# 3.net
KiCad netlist of a schematic drawn in EAGLE
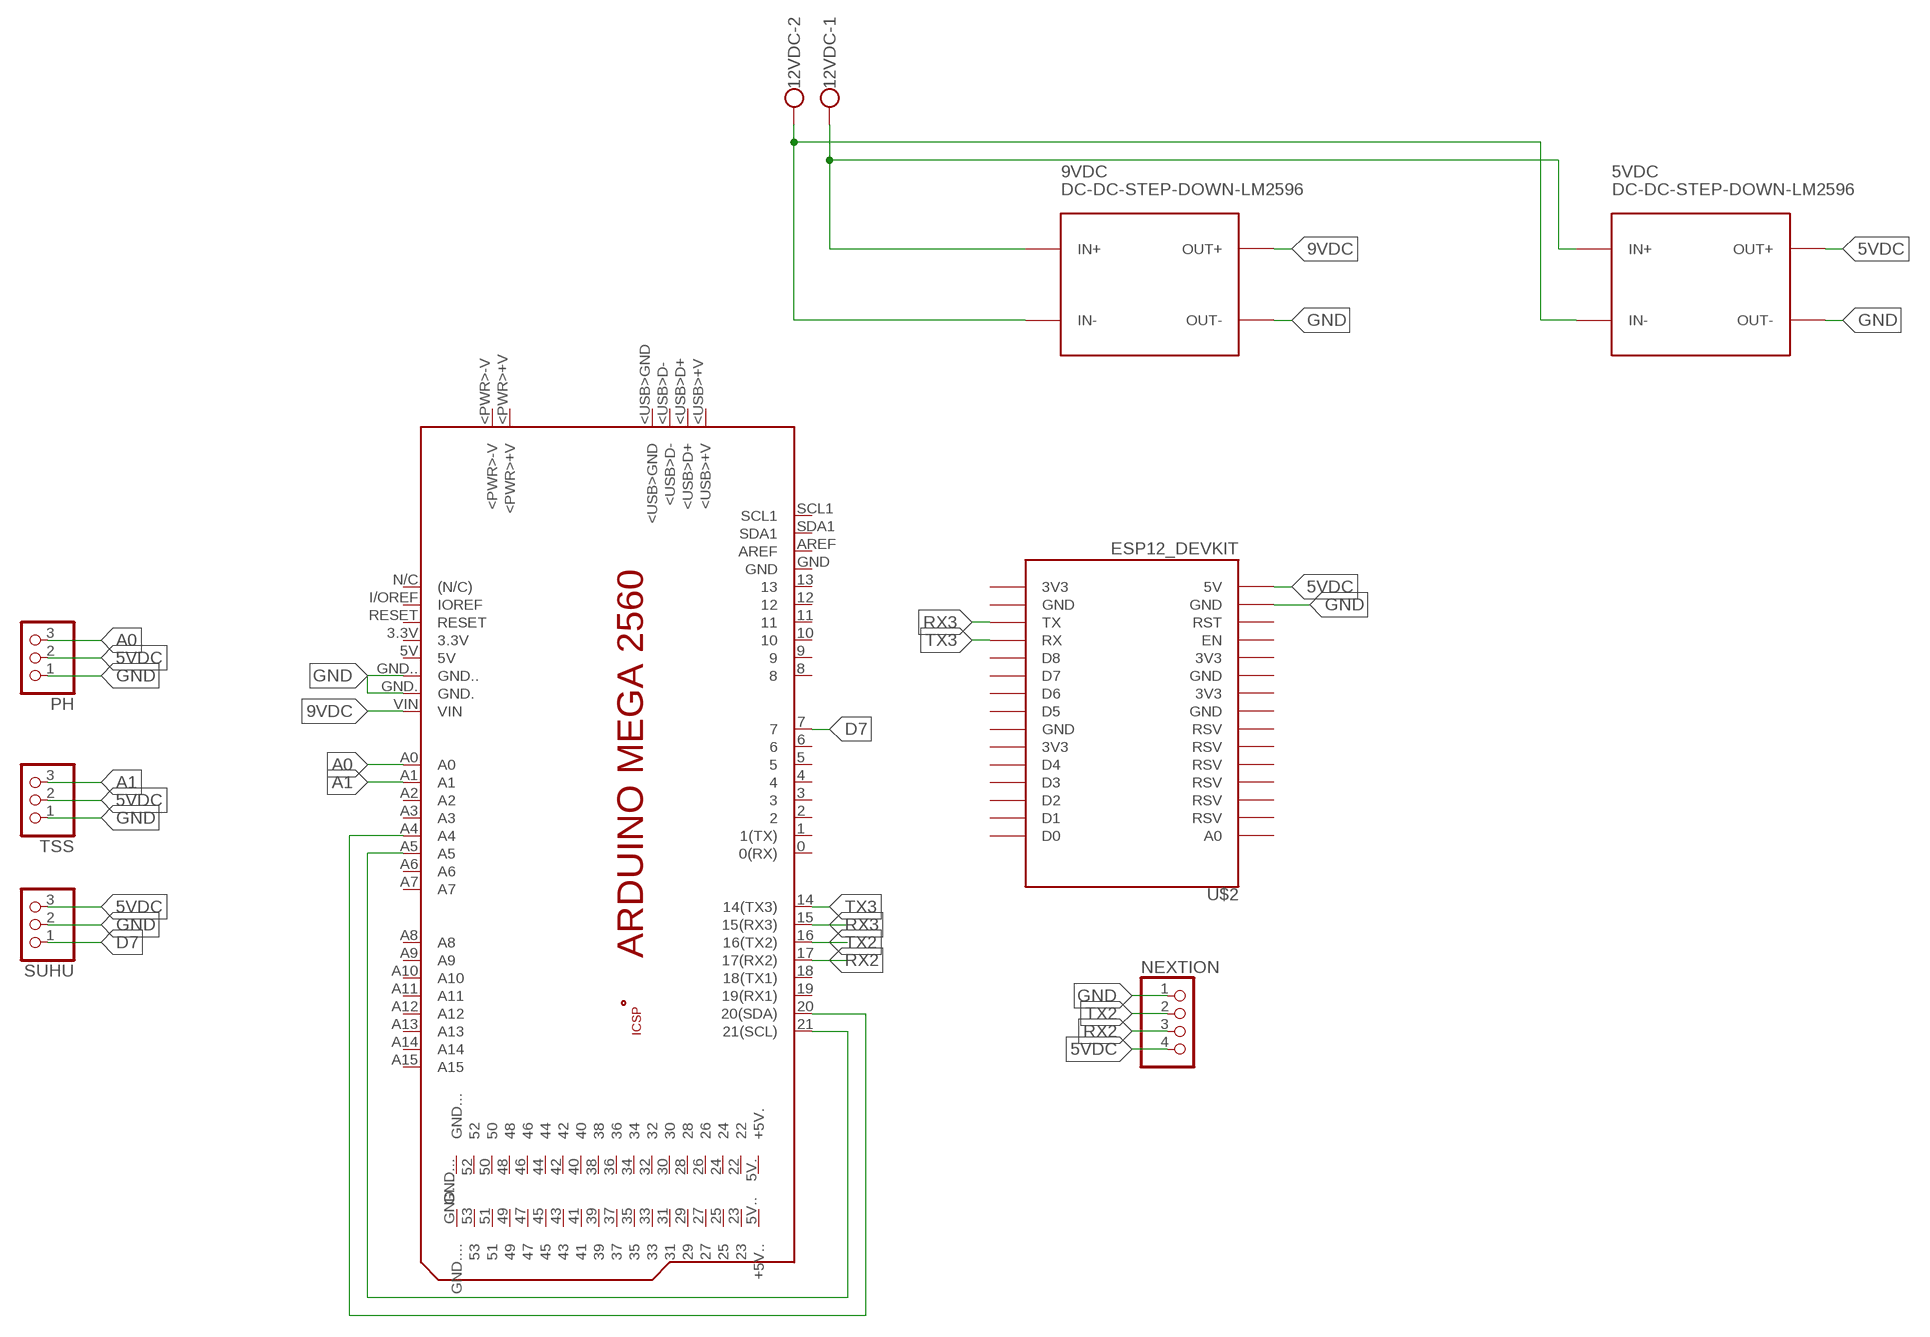
[diagram p0: schematic, sheet 1]

(export (version "E")
  (design (tool "Eeschema 10.0.6"))
  (components
    (comp (ref "5VDC")
      (value "DC-DC-STEP-DOWN-LM2596")
      (footprint "eagle-import:DC-DC-STEP-DOWN-LM2596")
      (libsource (lib "eagle-import") (part "DC-DC-STEP-DOWN-LM2596"))
    )
    (comp (ref "9VDC")
      (value "DC-DC-STEP-DOWN-LM2596")
      (footprint "eagle-import:DC-DC-STEP-DOWN-LM2596")
      (libsource (lib "eagle-import") (part "DC-DC-STEP-DOWN-LM2596"))
    )
    (comp (ref "12VDC")
      (value "W237-102")
      (footprint "eagle-import:W237-102")
      (fields (field (name "MPN") "237-102"))
      (libsource (lib "eagle-import") (part "W237-102"))
    )
    (comp (ref "NEXTION")
      (value "PINHD-1X4")
      (footprint "eagle-import:1X04")
      (libsource (lib "eagle-import") (part "PINHD-1X4"))
    )
    (comp (ref "PCB1")
      (value "ARDUINO_MEGA2560")
      (footprint "eagle-import:ARDUINO_MEGA2560")
      (libsource (lib "eagle-import") (part "ARDUINO_MEGA2560"))
    )
    (comp (ref "PH")
      (value "PINHD-1X3")
      (footprint "eagle-import:1X03")
      (libsource (lib "eagle-import") (part "PINHD-1X3"))
    )
    (comp (ref "SUHU")
      (value "PINHD-1X3")
      (footprint "eagle-import:1X03")
      (libsource (lib "eagle-import") (part "PINHD-1X3"))
    )
    (comp (ref "TSS")
      (value "PINHD-1X3")
      (footprint "eagle-import:1X03")
      (libsource (lib "eagle-import") (part "PINHD-1X3"))
    )
    (comp (ref "U$2")
      (value "ESP12_DEVKIT")
      (footprint "eagle-import:ESP12_DEVKIT")
      (libsource (lib "eagle-import") (part "ESP12_DEVKIT"))
    )
  )
  (nets
    (net (code "1") (name "5VDC") (class "Default")
      (node (ref "5VDC") (pin "OUT+") (pinfunction "OUT+_OUT+") (pintype "bidirectional"))
      (node (ref "NEXTION") (pin "4") (pinfunction "4_4") (pintype "passive"))
      (node (ref "PH") (pin "2") (pinfunction "2_2") (pintype "passive"))
      (node (ref "SUHU") (pin "3") (pinfunction "3_3") (pintype "passive"))
      (node (ref "TSS") (pin "2") (pinfunction "2_2") (pintype "passive"))
      (node (ref "U$2") (pin "5V") (pinfunction "5V_5V") (pintype "bidirectional"))
    )
    (net (code "2") (name "9VDC") (class "Default")
      (node (ref "9VDC") (pin "OUT+") (pinfunction "OUT+_OUT+") (pintype "bidirectional"))
      (node (ref "PCB1") (pin "VIN") (pinfunction "VIN_VIN") (pintype "bidirectional"))
    )
    (net (code "3") (name "A0") (class "Default")
      (node (ref "PCB1") (pin "A0") (pinfunction "A0_A0") (pintype "bidirectional"))
      (node (ref "PH") (pin "3") (pinfunction "3_3") (pintype "passive"))
    )
    (net (code "4") (name "A1") (class "Default")
      (node (ref "PCB1") (pin "A1") (pinfunction "A1_A1") (pintype "bidirectional"))
      (node (ref "TSS") (pin "3") (pinfunction "3_3") (pintype "passive"))
    )
    (net (code "5") (name "D7") (class "Default")
      (node (ref "PCB1") (pin "7") (pinfunction "7_7") (pintype "bidirectional"))
      (node (ref "SUHU") (pin "1") (pinfunction "1_1") (pintype "passive"))
    )
    (net (code "6") (name "GND") (class "Default")
      (node (ref "5VDC") (pin "OUT-") (pinfunction "OUT-_OUT-") (pintype "bidirectional"))
      (node (ref "9VDC") (pin "OUT-") (pinfunction "OUT-_OUT-") (pintype "bidirectional"))
      (node (ref "NEXTION") (pin "1") (pinfunction "1_1") (pintype "passive"))
      (node (ref "PCB1") (pin "GND.") (pinfunction "GND._GND.") (pintype "bidirectional"))
      (node (ref "PCB1") (pin "GND..") (pinfunction "GND.._GND..") (pintype "bidirectional"))
      (node (ref "PH") (pin "1") (pinfunction "1_1") (pintype "passive"))
      (node (ref "SUHU") (pin "2") (pinfunction "2_2") (pintype "passive"))
      (node (ref "TSS") (pin "1") (pinfunction "1_1") (pintype "passive"))
      (node (ref "U$2") (pin "GND@1") (pinfunction "GND_GND@1") (pintype "bidirectional"))
    )
    (net (code "7") (name "Net-(12VDCA-KL)") (class "Default")
      (node (ref "12VDC") (pin "1") (pinfunction "KL_1") (pintype "passive"))
      (node (ref "5VDC") (pin "IN+") (pinfunction "IN+_IN+") (pintype "bidirectional"))
      (node (ref "9VDC") (pin "IN+") (pinfunction "IN+_IN+") (pintype "bidirectional"))
    )
    (net (code "8") (name "Net-(12VDCB-KL)") (class "Default")
      (node (ref "12VDC") (pin "2") (pinfunction "KL_2") (pintype "passive"))
      (node (ref "5VDC") (pin "IN-") (pinfunction "IN-_IN-") (pintype "bidirectional"))
      (node (ref "9VDC") (pin "IN-") (pinfunction "IN-_IN-") (pintype "bidirectional"))
    )
    (net (code "9") (name "Net-(PCB1-20(SDA))") (class "Default")
      (node (ref "PCB1") (pin "20") (pinfunction "20(SDA)_20") (pintype "bidirectional"))
      (node (ref "PCB1") (pin "A4") (pinfunction "A4_A4") (pintype "bidirectional"))
    )
    (net (code "10") (name "Net-(PCB1-21(SCL))") (class "Default")
      (node (ref "PCB1") (pin "21") (pinfunction "21(SCL)_21") (pintype "bidirectional"))
      (node (ref "PCB1") (pin "A5") (pinfunction "A5_A5") (pintype "bidirectional"))
    )
    (net (code "11") (name "RX2") (class "Default")
      (node (ref "NEXTION") (pin "3") (pinfunction "3_3") (pintype "passive"))
      (node (ref "PCB1") (pin "17") (pinfunction "17(RX2)_17") (pintype "bidirectional"))
    )
    (net (code "12") (name "RX3") (class "Default")
      (node (ref "PCB1") (pin "15") (pinfunction "15(RX3)_15") (pintype "bidirectional"))
      (node (ref "U$2") (pin "TX") (pinfunction "TX_TX") (pintype "bidirectional"))
    )
    (net (code "13") (name "TX2") (class "Default")
      (node (ref "NEXTION") (pin "2") (pinfunction "2_2") (pintype "passive"))
      (node (ref "PCB1") (pin "16") (pinfunction "16(TX2)_16") (pintype "bidirectional"))
    )
    (net (code "14") (name "TX3") (class "Default")
      (node (ref "PCB1") (pin "14") (pinfunction "14(TX3)_14") (pintype "bidirectional"))
      (node (ref "U$2") (pin "RX") (pinfunction "RX_RX") (pintype "bidirectional"))
    )
    (net (code "15") (name "unconnected-(PCB1-(N{slash}C)-PadN{slash}C)") (class "Default")
      (node (ref "PCB1") (pin "N/C") (pinfunction "(N/C)_N/C") (pintype "bidirectional"))
    )
    (net (code "16") (name "unconnected-(PCB1-+5V.-Pad5V.)") (class "Default")
      (node (ref "PCB1") (pin "5V.") (pinfunction "+5V._5V.") (pintype "bidirectional"))
    )
    (net (code "17") (name "unconnected-(PCB1-+5V..-Pad5V..)") (class "Default")
      (node (ref "PCB1") (pin "5V..") (pinfunction "+5V.._5V..") (pintype "bidirectional"))
    )
    (net (code "18") (name "unconnected-(PCB1-0(RX)-Pad0)") (class "Default")
      (node (ref "PCB1") (pin "0") (pinfunction "0(RX)_0") (pintype "bidirectional"))
    )
    (net (code "19") (name "unconnected-(PCB1-1(TX)-Pad1)") (class "Default")
      (node (ref "PCB1") (pin "1") (pinfunction "1(TX)_1") (pintype "bidirectional"))
    )
    (net (code "20") (name "unconnected-(PCB1-18(TX1)-Pad18)") (class "Default")
      (node (ref "PCB1") (pin "18") (pinfunction "18(TX1)_18") (pintype "bidirectional"))
    )
    (net (code "21") (name "unconnected-(PCB1-19(RX1)-Pad19)") (class "Default")
      (node (ref "PCB1") (pin "19") (pinfunction "19(RX1)_19") (pintype "bidirectional"))
    )
    (net (code "22") (name "unconnected-(PCB1-IOREF-PadI{slash}OREF)") (class "Default")
      (node (ref "PCB1") (pin "I/OREF") (pinfunction "IOREF_I/OREF") (pintype "bidirectional"))
    )
    (net (code "23") (name "unconnected-(PCB1-Pad+5V_)") (class "Default")
      (node (ref "PCB1") (pin "+5V_") (pinfunction "+5V__+5V_") (pintype "bidirectional"))
    )
    (net (code "24") (name "unconnected-(PCB1-Pad2)") (class "Default")
      (node (ref "PCB1") (pin "2") (pinfunction "2_2") (pintype "bidirectional"))
    )
    (net (code "25") (name "unconnected-(PCB1-Pad3)") (class "Default")
      (node (ref "PCB1") (pin "3") (pinfunction "3_3") (pintype "bidirectional"))
    )
    (net (code "26") (name "unconnected-(PCB1-Pad3.3V)") (class "Default")
      (node (ref "PCB1") (pin "3.3V") (pinfunction "3.3V_3.3V") (pintype "bidirectional"))
    )
    (net (code "27") (name "unconnected-(PCB1-Pad4)") (class "Default")
      (node (ref "PCB1") (pin "4") (pinfunction "4_4") (pintype "bidirectional"))
    )
    (net (code "28") (name "unconnected-(PCB1-Pad5)") (class "Default")
      (node (ref "PCB1") (pin "5") (pinfunction "5_5") (pintype "bidirectional"))
    )
    (net (code "29") (name "unconnected-(PCB1-Pad5V)") (class "Default")
      (node (ref "PCB1") (pin "5V") (pinfunction "5V_5V") (pintype "bidirectional"))
    )
    (net (code "30") (name "unconnected-(PCB1-Pad6)") (class "Default")
      (node (ref "PCB1") (pin "6") (pinfunction "6_6") (pintype "bidirectional"))
    )
    (net (code "31") (name "unconnected-(PCB1-Pad8)") (class "Default")
      (node (ref "PCB1") (pin "8") (pinfunction "8_8") (pintype "bidirectional"))
    )
    (net (code "32") (name "unconnected-(PCB1-Pad9)") (class "Default")
      (node (ref "PCB1") (pin "9") (pinfunction "9_9") (pintype "bidirectional"))
    )
    (net (code "33") (name "unconnected-(PCB1-Pad10)") (class "Default")
      (node (ref "PCB1") (pin "10") (pinfunction "10_10") (pintype "bidirectional"))
    )
    (net (code "34") (name "unconnected-(PCB1-Pad11)") (class "Default")
      (node (ref "PCB1") (pin "11") (pinfunction "11_11") (pintype "bidirectional"))
    )
    (net (code "35") (name "unconnected-(PCB1-Pad12)") (class "Default")
      (node (ref "PCB1") (pin "12") (pinfunction "12_12") (pintype "bidirectional"))
    )
    (net (code "36") (name "unconnected-(PCB1-Pad13)") (class "Default")
      (node (ref "PCB1") (pin "13") (pinfunction "13_13") (pintype "bidirectional"))
    )
    (net (code "37") (name "unconnected-(PCB1-Pad22)") (class "Default")
      (node (ref "PCB1") (pin "22") (pinfunction "22_22") (pintype "bidirectional"))
    )
    (net (code "38") (name "unconnected-(PCB1-Pad23)") (class "Default")
      (node (ref "PCB1") (pin "23") (pinfunction "23_23") (pintype "bidirectional"))
    )
    (net (code "39") (name "unconnected-(PCB1-Pad24)") (class "Default")
      (node (ref "PCB1") (pin "24") (pinfunction "24_24") (pintype "bidirectional"))
    )
    (net (code "40") (name "unconnected-(PCB1-Pad25)") (class "Default")
      (node (ref "PCB1") (pin "25") (pinfunction "25_25") (pintype "bidirectional"))
    )
    (net (code "41") (name "unconnected-(PCB1-Pad26)") (class "Default")
      (node (ref "PCB1") (pin "26") (pinfunction "26_26") (pintype "bidirectional"))
    )
    (net (code "42") (name "unconnected-(PCB1-Pad27)") (class "Default")
      (node (ref "PCB1") (pin "27") (pinfunction "27_27") (pintype "bidirectional"))
    )
    (net (code "43") (name "unconnected-(PCB1-Pad28)") (class "Default")
      (node (ref "PCB1") (pin "28") (pinfunction "28_28") (pintype "bidirectional"))
    )
    (net (code "44") (name "unconnected-(PCB1-Pad29)") (class "Default")
      (node (ref "PCB1") (pin "29") (pinfunction "29_29") (pintype "bidirectional"))
    )
    (net (code "45") (name "unconnected-(PCB1-Pad30)") (class "Default")
      (node (ref "PCB1") (pin "30") (pinfunction "30_30") (pintype "bidirectional"))
    )
    (net (code "46") (name "unconnected-(PCB1-Pad31)") (class "Default")
      (node (ref "PCB1") (pin "31") (pinfunction "31_31") (pintype "bidirectional"))
    )
    (net (code "47") (name "unconnected-(PCB1-Pad32)") (class "Default")
      (node (ref "PCB1") (pin "32") (pinfunction "32_32") (pintype "bidirectional"))
    )
    (net (code "48") (name "unconnected-(PCB1-Pad33)") (class "Default")
      (node (ref "PCB1") (pin "33") (pinfunction "33_33") (pintype "bidirectional"))
    )
    (net (code "49") (name "unconnected-(PCB1-Pad34)") (class "Default")
      (node (ref "PCB1") (pin "34") (pinfunction "34_34") (pintype "bidirectional"))
    )
    (net (code "50") (name "unconnected-(PCB1-Pad35)") (class "Default")
      (node (ref "PCB1") (pin "35") (pinfunction "35_35") (pintype "bidirectional"))
    )
    (net (code "51") (name "unconnected-(PCB1-Pad36)") (class "Default")
      (node (ref "PCB1") (pin "36") (pinfunction "36_36") (pintype "bidirectional"))
    )
    (net (code "52") (name "unconnected-(PCB1-Pad37)") (class "Default")
      (node (ref "PCB1") (pin "37") (pinfunction "37_37") (pintype "bidirectional"))
    )
    (net (code "53") (name "unconnected-(PCB1-Pad38)") (class "Default")
      (node (ref "PCB1") (pin "38") (pinfunction "38_38") (pintype "bidirectional"))
    )
    (net (code "54") (name "unconnected-(PCB1-Pad39)") (class "Default")
      (node (ref "PCB1") (pin "39") (pinfunction "39_39") (pintype "bidirectional"))
    )
    (net (code "55") (name "unconnected-(PCB1-Pad40)") (class "Default")
      (node (ref "PCB1") (pin "40") (pinfunction "40_40") (pintype "bidirectional"))
    )
    (net (code "56") (name "unconnected-(PCB1-Pad41)") (class "Default")
      (node (ref "PCB1") (pin "41") (pinfunction "41_41") (pintype "bidirectional"))
    )
    (net (code "57") (name "unconnected-(PCB1-Pad42)") (class "Default")
      (node (ref "PCB1") (pin "42") (pinfunction "42_42") (pintype "bidirectional"))
    )
    (net (code "58") (name "unconnected-(PCB1-Pad43)") (class "Default")
      (node (ref "PCB1") (pin "43") (pinfunction "43_43") (pintype "bidirectional"))
    )
    (net (code "59") (name "unconnected-(PCB1-Pad44)") (class "Default")
      (node (ref "PCB1") (pin "44") (pinfunction "44_44") (pintype "bidirectional"))
    )
    (net (code "60") (name "unconnected-(PCB1-Pad45)") (class "Default")
      (node (ref "PCB1") (pin "45") (pinfunction "45_45") (pintype "bidirectional"))
    )
    (net (code "61") (name "unconnected-(PCB1-Pad46)") (class "Default")
      (node (ref "PCB1") (pin "46") (pinfunction "46_46") (pintype "bidirectional"))
    )
    (net (code "62") (name "unconnected-(PCB1-Pad47)") (class "Default")
      (node (ref "PCB1") (pin "47") (pinfunction "47_47") (pintype "bidirectional"))
    )
    (net (code "63") (name "unconnected-(PCB1-Pad48)") (class "Default")
      (node (ref "PCB1") (pin "48") (pinfunction "48_48") (pintype "bidirectional"))
    )
    (net (code "64") (name "unconnected-(PCB1-Pad49)") (class "Default")
      (node (ref "PCB1") (pin "49") (pinfunction "49_49") (pintype "bidirectional"))
    )
    (net (code "65") (name "unconnected-(PCB1-Pad50)") (class "Default")
      (node (ref "PCB1") (pin "50") (pinfunction "50_50") (pintype "bidirectional"))
    )
    (net (code "66") (name "unconnected-(PCB1-Pad51)") (class "Default")
      (node (ref "PCB1") (pin "51") (pinfunction "51_51") (pintype "bidirectional"))
    )
    (net (code "67") (name "unconnected-(PCB1-Pad52)") (class "Default")
      (node (ref "PCB1") (pin "52") (pinfunction "52_52") (pintype "bidirectional"))
    )
    (net (code "68") (name "unconnected-(PCB1-Pad53)") (class "Default")
      (node (ref "PCB1") (pin "53") (pinfunction "53_53") (pintype "bidirectional"))
    )
    (net (code "69") (name "unconnected-(PCB1-Pad<PWR>+V)") (class "Default")
      (node (ref "PCB1") (pin "<PWR>+V") (pinfunction "<PWR>+V_<PWR>+V") (pintype "no_connect"))
    )
    (net (code "70") (name "unconnected-(PCB1-Pad<PWR>-V)") (class "Default")
      (node (ref "PCB1") (pin "<PWR>-V") (pinfunction "<PWR>-V_<PWR>-V") (pintype "no_connect"))
    )
    (net (code "71") (name "unconnected-(PCB1-Pad<USB>+V)") (class "Default")
      (node (ref "PCB1") (pin "<USB>+V") (pinfunction "<USB>+V_<USB>+V") (pintype "no_connect"))
    )
    (net (code "72") (name "unconnected-(PCB1-Pad<USB>D+)") (class "Default")
      (node (ref "PCB1") (pin "<USB>D+") (pinfunction "<USB>D+_<USB>D+") (pintype "no_connect"))
    )
    (net (code "73") (name "unconnected-(PCB1-Pad<USB>D-)") (class "Default")
      (node (ref "PCB1") (pin "<USB>D-") (pinfunction "<USB>D-_<USB>D-") (pintype "no_connect"))
    )
    (net (code "74") (name "unconnected-(PCB1-Pad<USB>GND)") (class "Default")
      (node (ref "PCB1") (pin "<USB>GND") (pinfunction "<USB>GND_<USB>GND") (pintype "no_connect"))
    )
    (net (code "75") (name "unconnected-(PCB1-PadA2)") (class "Default")
      (node (ref "PCB1") (pin "A2") (pinfunction "A2_A2") (pintype "bidirectional"))
    )
    (net (code "76") (name "unconnected-(PCB1-PadA3)") (class "Default")
      (node (ref "PCB1") (pin "A3") (pinfunction "A3_A3") (pintype "bidirectional"))
    )
    (net (code "77") (name "unconnected-(PCB1-PadA6)") (class "Default")
      (node (ref "PCB1") (pin "A6") (pinfunction "A6_A6") (pintype "bidirectional"))
    )
    (net (code "78") (name "unconnected-(PCB1-PadA7)") (class "Default")
      (node (ref "PCB1") (pin "A7") (pinfunction "A7_A7") (pintype "bidirectional"))
    )
    (net (code "79") (name "unconnected-(PCB1-PadA8)") (class "Default")
      (node (ref "PCB1") (pin "A8") (pinfunction "A8_A8") (pintype "bidirectional"))
    )
    (net (code "80") (name "unconnected-(PCB1-PadA9)") (class "Default")
      (node (ref "PCB1") (pin "A9") (pinfunction "A9_A9") (pintype "bidirectional"))
    )
    (net (code "81") (name "unconnected-(PCB1-PadA10)") (class "Default")
      (node (ref "PCB1") (pin "A10") (pinfunction "A10_A10") (pintype "bidirectional"))
    )
    (net (code "82") (name "unconnected-(PCB1-PadA11)") (class "Default")
      (node (ref "PCB1") (pin "A11") (pinfunction "A11_A11") (pintype "bidirectional"))
    )
    (net (code "83") (name "unconnected-(PCB1-PadA12)") (class "Default")
      (node (ref "PCB1") (pin "A12") (pinfunction "A12_A12") (pintype "bidirectional"))
    )
    (net (code "84") (name "unconnected-(PCB1-PadA13)") (class "Default")
      (node (ref "PCB1") (pin "A13") (pinfunction "A13_A13") (pintype "bidirectional"))
    )
    (net (code "85") (name "unconnected-(PCB1-PadA14)") (class "Default")
      (node (ref "PCB1") (pin "A14") (pinfunction "A14_A14") (pintype "bidirectional"))
    )
    (net (code "86") (name "unconnected-(PCB1-PadA15)") (class "Default")
      (node (ref "PCB1") (pin "A15") (pinfunction "A15_A15") (pintype "bidirectional"))
    )
    (net (code "87") (name "unconnected-(PCB1-PadAREF)") (class "Default")
      (node (ref "PCB1") (pin "AREF") (pinfunction "AREF_AREF") (pintype "bidirectional"))
    )
    (net (code "88") (name "unconnected-(PCB1-PadGND)") (class "Default")
      (node (ref "PCB1") (pin "GND") (pinfunction "GND_GND") (pintype "bidirectional"))
    )
    (net (code "89") (name "unconnected-(PCB1-PadGND...)") (class "Default")
      (node (ref "PCB1") (pin "GND...") (pinfunction "GND..._GND...") (pintype "bidirectional"))
    )
    (net (code "90") (name "unconnected-(PCB1-PadGND....)") (class "Default")
      (node (ref "PCB1") (pin "GND....") (pinfunction "GND...._GND....") (pintype "bidirectional"))
    )
    (net (code "91") (name "unconnected-(PCB1-PadGND__)") (class "Default")
      (node (ref "PCB1") (pin "GND__") (pinfunction "GND___GND__") (pintype "bidirectional"))
    )
    (net (code "92") (name "unconnected-(PCB1-PadMISO)") (class "Default")
      (node (ref "PCB1") (pin "MISO") (pinfunction "MISO_MISO") (pintype "bidirectional"))
    )
    (net (code "93") (name "unconnected-(PCB1-PadMOSI)") (class "Default")
      (node (ref "PCB1") (pin "MOSI") (pinfunction "MOSI_MOSI") (pintype "bidirectional"))
    )
    (net (code "94") (name "unconnected-(PCB1-PadRESET)") (class "Default")
      (node (ref "PCB1") (pin "RESET") (pinfunction "RESET_RESET") (pintype "bidirectional"))
    )
    (net (code "95") (name "unconnected-(PCB1-PadRESET.)") (class "Default")
      (node (ref "PCB1") (pin "RESET.") (pinfunction "RESET._RESET.") (pintype "bidirectional"))
    )
    (net (code "96") (name "unconnected-(PCB1-PadSCK)") (class "Default")
      (node (ref "PCB1") (pin "SCK") (pinfunction "SCK_SCK") (pintype "bidirectional"))
    )
    (net (code "97") (name "unconnected-(PCB1-PadSCL1)") (class "Default")
      (node (ref "PCB1") (pin "SCL1") (pinfunction "SCL1_SCL1") (pintype "bidirectional"))
    )
    (net (code "98") (name "unconnected-(PCB1-PadSDA1)") (class "Default")
      (node (ref "PCB1") (pin "SDA1") (pinfunction "SDA1_SDA1") (pintype "bidirectional"))
    )
    (net (code "99") (name "unconnected-(U$2-3V3-Pad3V3@0)") (class "Default")
      (node (ref "U$2") (pin "3V3@0") (pinfunction "3V3_3V3@0") (pintype "bidirectional"))
    )
    (net (code "100") (name "unconnected-(U$2-3V3-Pad3V3@1)") (class "Default")
      (node (ref "U$2") (pin "3V3@1") (pinfunction "3V3_3V3@1") (pintype "bidirectional"))
    )
    (net (code "101") (name "unconnected-(U$2-3V3-Pad3V3@2)") (class "Default")
      (node (ref "U$2") (pin "3V3@2") (pinfunction "3V3_3V3@2") (pintype "bidirectional"))
    )
    (net (code "102") (name "unconnected-(U$2-3V3-Pad3V3@3)") (class "Default")
      (node (ref "U$2") (pin "3V3@3") (pinfunction "3V3_3V3@3") (pintype "bidirectional"))
    )
    (net (code "103") (name "unconnected-(U$2-GND-PadGND@0)") (class "Default")
      (node (ref "U$2") (pin "GND@0") (pinfunction "GND_GND@0") (pintype "bidirectional"))
    )
    (net (code "104") (name "unconnected-(U$2-GND-PadGND@2)") (class "Default")
      (node (ref "U$2") (pin "GND@2") (pinfunction "GND_GND@2") (pintype "bidirectional"))
    )
    (net (code "105") (name "unconnected-(U$2-GND-PadGND@3)") (class "Default")
      (node (ref "U$2") (pin "GND@3") (pinfunction "GND_GND@3") (pintype "bidirectional"))
    )
    (net (code "106") (name "unconnected-(U$2-GND-PadGND@4)") (class "Default")
      (node (ref "U$2") (pin "GND@4") (pinfunction "GND_GND@4") (pintype "bidirectional"))
    )
    (net (code "107") (name "unconnected-(U$2-PadA0)") (class "Default")
      (node (ref "U$2") (pin "A0") (pinfunction "A0_A0") (pintype "bidirectional"))
    )
    (net (code "108") (name "unconnected-(U$2-PadD0)") (class "Default")
      (node (ref "U$2") (pin "D0") (pinfunction "D0_D0") (pintype "bidirectional"))
    )
    (net (code "109") (name "unconnected-(U$2-PadD1)") (class "Default")
      (node (ref "U$2") (pin "D1") (pinfunction "D1_D1") (pintype "bidirectional"))
    )
    (net (code "110") (name "unconnected-(U$2-PadD2)") (class "Default")
      (node (ref "U$2") (pin "D2") (pinfunction "D2_D2") (pintype "bidirectional"))
    )
    (net (code "111") (name "unconnected-(U$2-PadD3)") (class "Default")
      (node (ref "U$2") (pin "D3") (pinfunction "D3_D3") (pintype "bidirectional"))
    )
    (net (code "112") (name "unconnected-(U$2-PadD4)") (class "Default")
      (node (ref "U$2") (pin "D4") (pinfunction "D4_D4") (pintype "bidirectional"))
    )
    (net (code "113") (name "unconnected-(U$2-PadD5)") (class "Default")
      (node (ref "U$2") (pin "D5") (pinfunction "D5_D5") (pintype "bidirectional"))
    )
    (net (code "114") (name "unconnected-(U$2-PadD6)") (class "Default")
      (node (ref "U$2") (pin "D6") (pinfunction "D6_D6") (pintype "bidirectional"))
    )
    (net (code "115") (name "unconnected-(U$2-PadD7)") (class "Default")
      (node (ref "U$2") (pin "D7") (pinfunction "D7_D7") (pintype "bidirectional"))
    )
    (net (code "116") (name "unconnected-(U$2-PadD8)") (class "Default")
      (node (ref "U$2") (pin "D8") (pinfunction "D8_D8") (pintype "bidirectional"))
    )
    (net (code "117") (name "unconnected-(U$2-PadEN)") (class "Default")
      (node (ref "U$2") (pin "EN") (pinfunction "EN_EN") (pintype "bidirectional"))
    )
    (net (code "118") (name "unconnected-(U$2-PadRST)") (class "Default")
      (node (ref "U$2") (pin "RST") (pinfunction "RST_RST") (pintype "bidirectional"))
    )
    (net (code "119") (name "unconnected-(U$2-RSV-PadRSV@0)") (class "Default")
      (node (ref "U$2") (pin "RSV@0") (pinfunction "RSV_RSV@0") (pintype "bidirectional"))
    )
    (net (code "120") (name "unconnected-(U$2-RSV-PadRSV@1)") (class "Default")
      (node (ref "U$2") (pin "RSV@1") (pinfunction "RSV_RSV@1") (pintype "bidirectional"))
    )
    (net (code "121") (name "unconnected-(U$2-RSV-PadRSV@2)") (class "Default")
      (node (ref "U$2") (pin "RSV@2") (pinfunction "RSV_RSV@2") (pintype "bidirectional"))
    )
    (net (code "122") (name "unconnected-(U$2-RSV-PadRSV@3)") (class "Default")
      (node (ref "U$2") (pin "RSV@3") (pinfunction "RSV_RSV@3") (pintype "bidirectional"))
    )
    (net (code "123") (name "unconnected-(U$2-RSV-PadRSV@4)") (class "Default")
      (node (ref "U$2") (pin "RSV@4") (pinfunction "RSV_RSV@4") (pintype "bidirectional"))
    )
    (net (code "124") (name "unconnected-(U$2-RSV-PadRSV@5)") (class "Default")
      (node (ref "U$2") (pin "RSV@5") (pinfunction "RSV_RSV@5") (pintype "bidirectional"))
    )
  )
)
